# Adafruit_BMP581_Temperature_and_Pressure.net
KiCad netlist of a schematic drawn in EAGLE
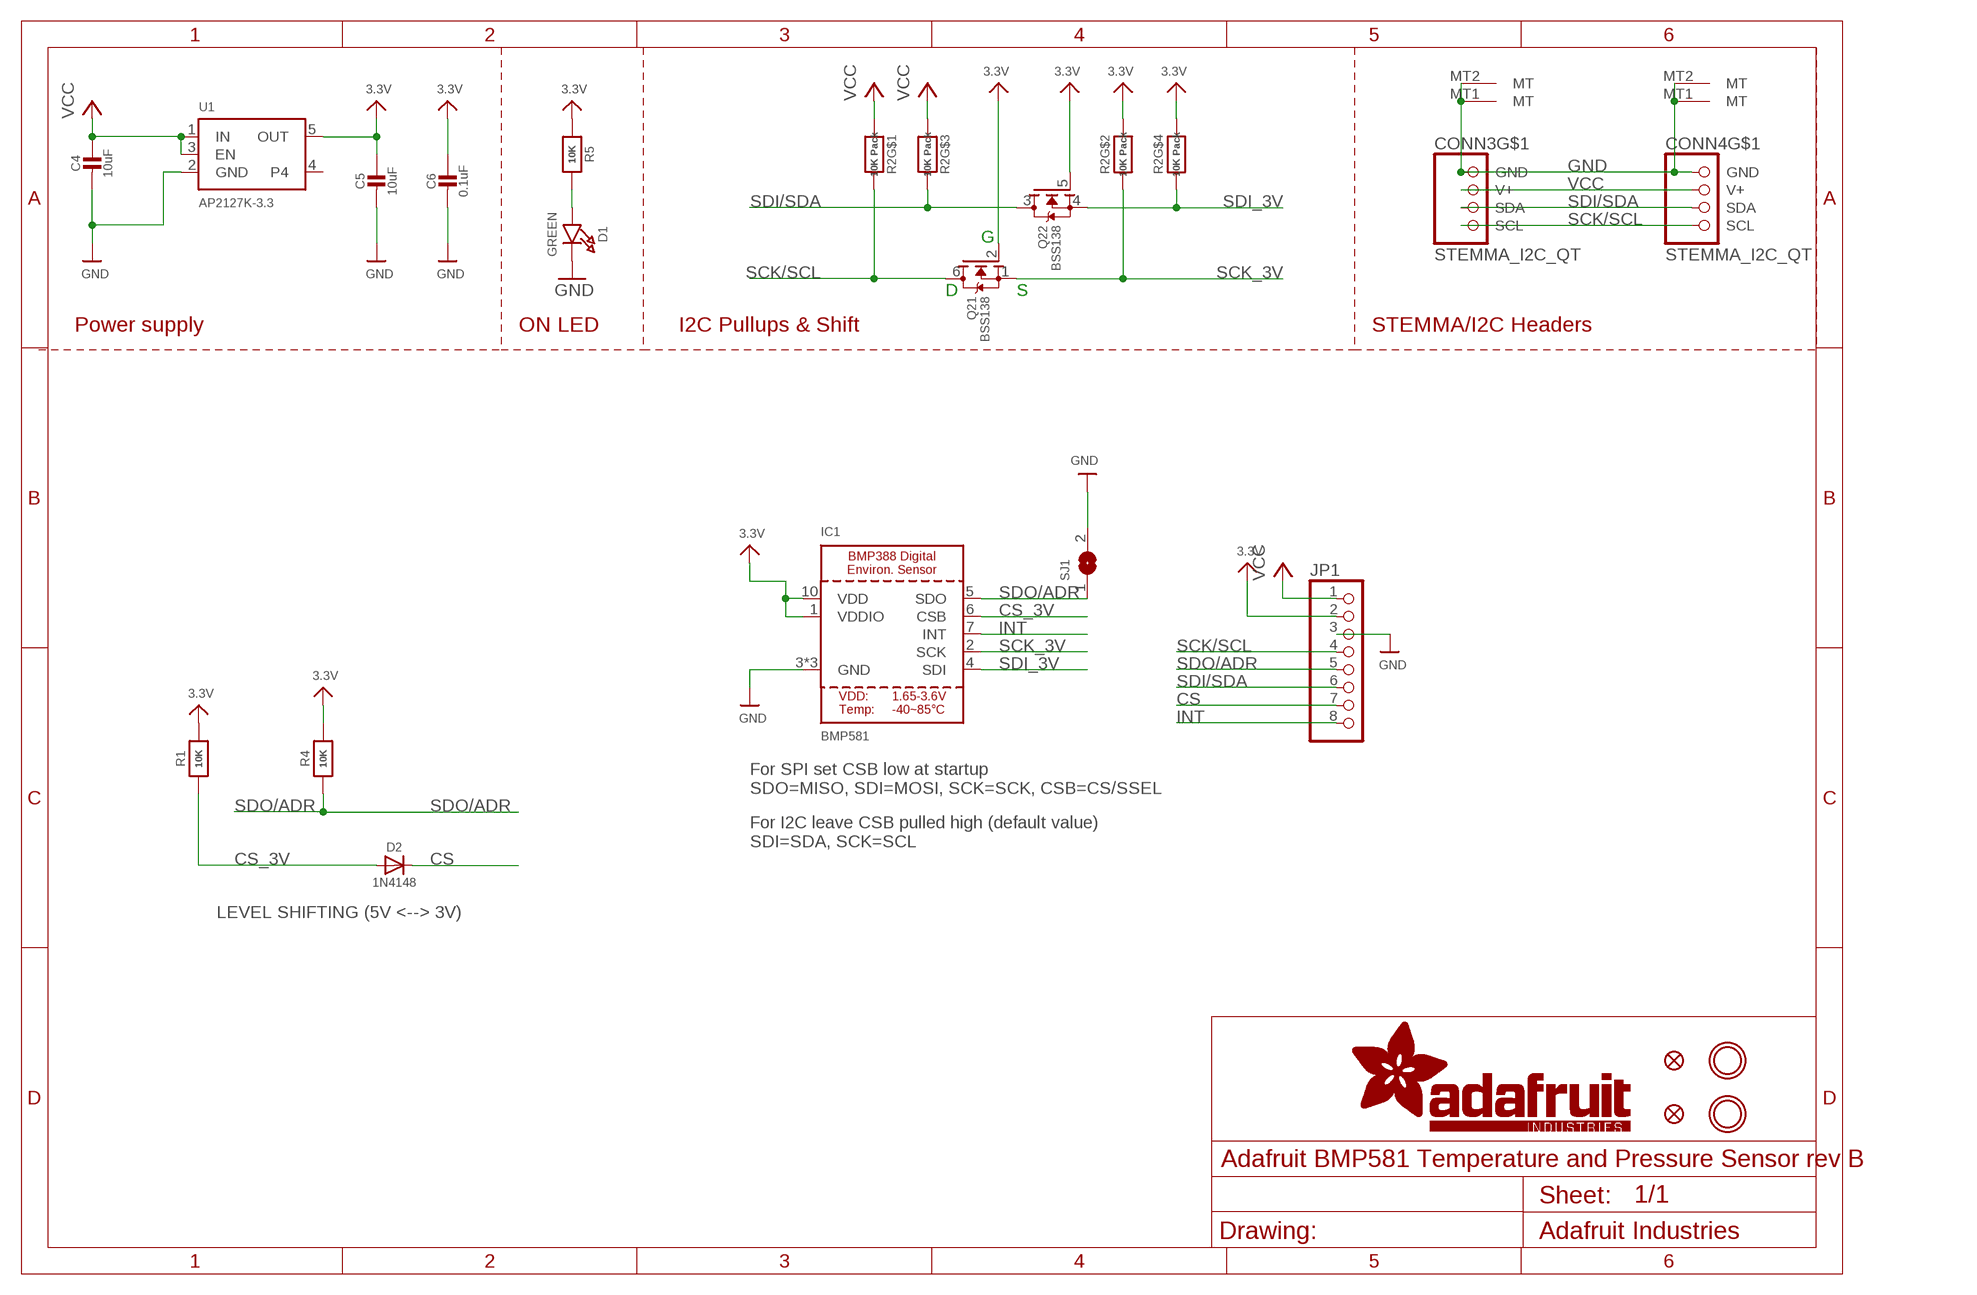
[diagram p0: schematic, sheet 1]

(export (version "E")
  (design (tool "Eeschema 10.0.6"))
  (components
    (comp (ref "C4")
      (value "10uF")
      (footprint "eagle-import:0805-NO")
      (libsource (lib "eagle-import") (part "CAP_CERAMIC0805-NOOUTLINE"))
    )
    (comp (ref "C5")
      (value "10uF")
      (footprint "eagle-import:0805-NO")
      (libsource (lib "eagle-import") (part "CAP_CERAMIC0805-NOOUTLINE"))
    )
    (comp (ref "C6")
      (value "0.1uF")
      (footprint "eagle-import:0603-NO")
      (libsource (lib "eagle-import") (part "CAP_CERAMIC0603_NO"))
    )
    (comp (ref "CONN3")
      (value "STEMMA_I2C_QT")
      (footprint "eagle-import:JST_SH4")
      (libsource (lib "eagle-import") (part "STEMMA_I2C_QT"))
    )
    (comp (ref "CONN4")
      (value "STEMMA_I2C_QT")
      (footprint "eagle-import:JST_SH4")
      (libsource (lib "eagle-import") (part "STEMMA_I2C_QT"))
    )
    (comp (ref "D1")
      (value "GREEN")
      (footprint "eagle-import:CHIPLED_0603_NOOUTLINE")
      (libsource (lib "eagle-import") (part "LED0603_NOOUTLINE"))
    )
    (comp (ref "D2")
      (value "1N4148")
      (footprint "eagle-import:SOD-323")
      (libsource (lib "eagle-import") (part "DIODESOD-323"))
    )
    (comp (ref "FID3")
      (value "FIDUCIAL_1MM")
      (footprint "eagle-import:FIDUCIAL_1MM")
      (libsource (lib "eagle-import") (part "FIDUCIAL_1MM"))
    )
    (comp (ref "FID4")
      (value "FIDUCIAL_1MM")
      (footprint "eagle-import:FIDUCIAL_1MM")
      (libsource (lib "eagle-import") (part "FIDUCIAL_1MM"))
    )
    (comp (ref "IC1")
      (value "BMP581")
      (footprint "eagle-import:BMP388")
      (libsource (lib "eagle-import") (part "BMP388"))
    )
    (comp (ref "JP1")
      (value "HEADER-1X870MIL")
      (footprint "eagle-import:1X08_ROUND_70")
      (libsource (lib "eagle-import") (part "HEADER-1X870MIL"))
    )
    (comp (ref "Q2")
      (value "BSS138")
      (footprint "eagle-import:SOT363")
      (libsource (lib "eagle-import") (part "MOSFET-N_DUAL"))
    )
    (comp (ref "R1")
      (value "10K")
      (footprint "eagle-import:0603-NO")
      (libsource (lib "eagle-import") (part "RESISTOR_0603_NOOUT"))
    )
    (comp (ref "R2")
      (value "10K Pack")
      (footprint "eagle-import:RESPACK_4X0603")
      (libsource (lib "eagle-import") (part "RESISTOR_4PACK"))
    )
    (comp (ref "R4")
      (value "10K")
      (footprint "eagle-import:0603-NO")
      (libsource (lib "eagle-import") (part "RESISTOR_0603_NOOUT"))
    )
    (comp (ref "R5")
      (value "10K")
      (footprint "eagle-import:0603-NO")
      (libsource (lib "eagle-import") (part "RESISTOR_0603_NOOUT"))
    )
    (comp (ref "SJ1")
      (value "SOLDERJUMPER")
      (footprint "eagle-import:SOLDERJUMPER_ARROW_NOPASTE")
      (libsource (lib "eagle-import") (part "SOLDERJUMPER"))
    )
    (comp (ref "U$40")
      (value "MOUNTINGHOLE2.5")
      (footprint "eagle-import:MOUNTINGHOLE_2.5_PLATED")
      (libsource (lib "eagle-import") (part "MOUNTINGHOLE2.5"))
    )
    (comp (ref "U$41")
      (value "MOUNTINGHOLE2.5")
      (footprint "eagle-import:MOUNTINGHOLE_2.5_PLATED")
      (libsource (lib "eagle-import") (part "MOUNTINGHOLE2.5"))
    )
    (comp (ref "U1")
      (value "AP2127K-3.3")
      (footprint "eagle-import:SOT23-5")
      (libsource (lib "eagle-import") (part "VREG_SOT23-5"))
    )
  )
  (nets
    (net (code "1") (name "/CS") (class "Default")
      (node (ref "D2") (pin "C") (pinfunction "C_C") (pintype "passive"))
      (node (ref "JP1") (pin "7") (pinfunction "7_7") (pintype "passive"))
    )
    (net (code "2") (name "/CS_3V") (class "Default")
      (node (ref "D2") (pin "A") (pinfunction "A_A") (pintype "passive"))
      (node (ref "IC1") (pin "6") (pinfunction "CSB_6") (pintype "input"))
      (node (ref "R1") (pin "1") (pinfunction "1_1") (pintype "passive"))
    )
    (net (code "3") (name "/INT") (class "Default")
      (node (ref "IC1") (pin "7") (pinfunction "INT_7") (pintype "output"))
      (node (ref "JP1") (pin "8") (pinfunction "8_8") (pintype "passive"))
    )
    (net (code "4") (name "/SCK_3V") (class "Default")
      (node (ref "IC1") (pin "2") (pinfunction "SCK_2") (pintype "input"))
      (node (ref "Q2") (pin "1") (pinfunction "S_1") (pintype "bidirectional"))
      (node (ref "R2") (pin "7") (pinfunction "2_7") (pintype "passive"))
    )
    (net (code "5") (name "/SCK{slash}SCL") (class "Default")
      (node (ref "CONN3") (pin "4") (pinfunction "SCL_4") (pintype "passive"))
      (node (ref "CONN4") (pin "4") (pinfunction "SCL_4") (pintype "passive"))
      (node (ref "JP1") (pin "4") (pinfunction "4_4") (pintype "passive"))
      (node (ref "Q2") (pin "6") (pinfunction "D_6") (pintype "bidirectional"))
      (node (ref "R2") (pin "8") (pinfunction "2_8") (pintype "passive"))
    )
    (net (code "6") (name "/SDI_3V") (class "Default")
      (node (ref "IC1") (pin "4") (pinfunction "SDI_4") (pintype "input"))
      (node (ref "Q2") (pin "4") (pinfunction "S_4") (pintype "bidirectional"))
      (node (ref "R2") (pin "5") (pinfunction "2_5") (pintype "passive"))
    )
    (net (code "7") (name "/SDI{slash}SDA") (class "Default")
      (node (ref "CONN3") (pin "3") (pinfunction "SDA_3") (pintype "passive"))
      (node (ref "CONN4") (pin "3") (pinfunction "SDA_3") (pintype "passive"))
      (node (ref "JP1") (pin "6") (pinfunction "6_6") (pintype "passive"))
      (node (ref "Q2") (pin "3") (pinfunction "D_3") (pintype "bidirectional"))
      (node (ref "R2") (pin "6") (pinfunction "2_6") (pintype "passive"))
    )
    (net (code "8") (name "/SDO{slash}ADR") (class "Default")
      (node (ref "IC1") (pin "5") (pinfunction "SDO_5") (pintype "output"))
      (node (ref "JP1") (pin "5") (pinfunction "5_5") (pintype "passive"))
      (node (ref "R4") (pin "1") (pinfunction "1_1") (pintype "passive"))
      (node (ref "SJ1") (pin "1") (pinfunction "1_1") (pintype "passive"))
    )
    (net (code "9") (name "3.3V") (class "Default")
      (node (ref "C5") (pin "1") (pinfunction "1_1") (pintype "passive"))
      (node (ref "C6") (pin "1") (pinfunction "1_1") (pintype "passive"))
      (node (ref "IC1") (pin "1") (pinfunction "VDDIO_1") (pintype "power_in"))
      (node (ref "IC1") (pin "10") (pinfunction "VDD_10") (pintype "power_in"))
      (node (ref "JP1") (pin "2") (pinfunction "2_2") (pintype "passive"))
      (node (ref "Q2") (pin "2") (pinfunction "G_2") (pintype "bidirectional"))
      (node (ref "Q2") (pin "5") (pinfunction "G_5") (pintype "bidirectional"))
      (node (ref "R1") (pin "2") (pinfunction "2_2") (pintype "passive"))
      (node (ref "R2") (pin "2") (pinfunction "1_2") (pintype "passive"))
      (node (ref "R2") (pin "4") (pinfunction "1_4") (pintype "passive"))
      (node (ref "R4") (pin "2") (pinfunction "2_2") (pintype "passive"))
      (node (ref "R5") (pin "1") (pinfunction "1_1") (pintype "passive"))
      (node (ref "U1") (pin "5") (pinfunction "OUT_5") (pintype "power_in"))
    )
    (net (code "10") (name "GND") (class "Default")
      (node (ref "C4") (pin "2") (pinfunction "2_2") (pintype "passive"))
      (node (ref "C5") (pin "2") (pinfunction "2_2") (pintype "passive"))
      (node (ref "C6") (pin "2") (pinfunction "2_2") (pintype "passive"))
      (node (ref "CONN3") (pin "1") (pinfunction "GND_1") (pintype "passive"))
      (node (ref "CONN3") (pin "MT1") (pinfunction "MT_MT1") (pintype "bidirectional"))
      (node (ref "CONN3") (pin "MT2") (pinfunction "MT_MT2") (pintype "bidirectional"))
      (node (ref "CONN4") (pin "1") (pinfunction "GND_1") (pintype "passive"))
      (node (ref "CONN4") (pin "MT1") (pinfunction "MT_MT1") (pintype "bidirectional"))
      (node (ref "CONN4") (pin "MT2") (pinfunction "MT_MT2") (pintype "bidirectional"))
      (node (ref "D1") (pin "C") (pinfunction "C_C") (pintype "passive"))
      (node (ref "IC1") (pin "3") (pinfunction "GND_3") (pintype "power_in"))
      (node (ref "IC1") (pin "8") (pinfunction "GND_8") (pintype "power_in"))
      (node (ref "IC1") (pin "9") (pinfunction "GND_9") (pintype "power_in"))
      (node (ref "JP1") (pin "3") (pinfunction "3_3") (pintype "passive"))
      (node (ref "SJ1") (pin "2") (pinfunction "2_2") (pintype "passive"))
      (node (ref "U1") (pin "2") (pinfunction "GND_2") (pintype "power_in"))
    )
    (net (code "11") (name "Net-(D1-PadA)") (class "Default")
      (node (ref "D1") (pin "A") (pinfunction "A_A") (pintype "passive"))
      (node (ref "R5") (pin "2") (pinfunction "2_2") (pintype "passive"))
    )
    (net (code "12") (name "VCC") (class "Default")
      (node (ref "C4") (pin "1") (pinfunction "1_1") (pintype "passive"))
      (node (ref "CONN3") (pin "2") (pinfunction "V+_2") (pintype "passive"))
      (node (ref "CONN4") (pin "2") (pinfunction "V+_2") (pintype "passive"))
      (node (ref "JP1") (pin "1") (pinfunction "1_1") (pintype "passive"))
      (node (ref "R2") (pin "1") (pinfunction "1_1") (pintype "passive"))
      (node (ref "R2") (pin "3") (pinfunction "1_3") (pintype "passive"))
      (node (ref "U1") (pin "1") (pinfunction "IN_1") (pintype "power_in"))
      (node (ref "U1") (pin "3") (pinfunction "EN_3") (pintype "input"))
    )
    (net (code "13") (name "unconnected-(U1-P4-Pad4)") (class "Default")
      (node (ref "U1") (pin "4") (pinfunction "P4_4") (pintype "bidirectional"))
    )
  )
)
